# RFMC_ADC.net
KiCad netlist of a schematic drawn in Altium Designer
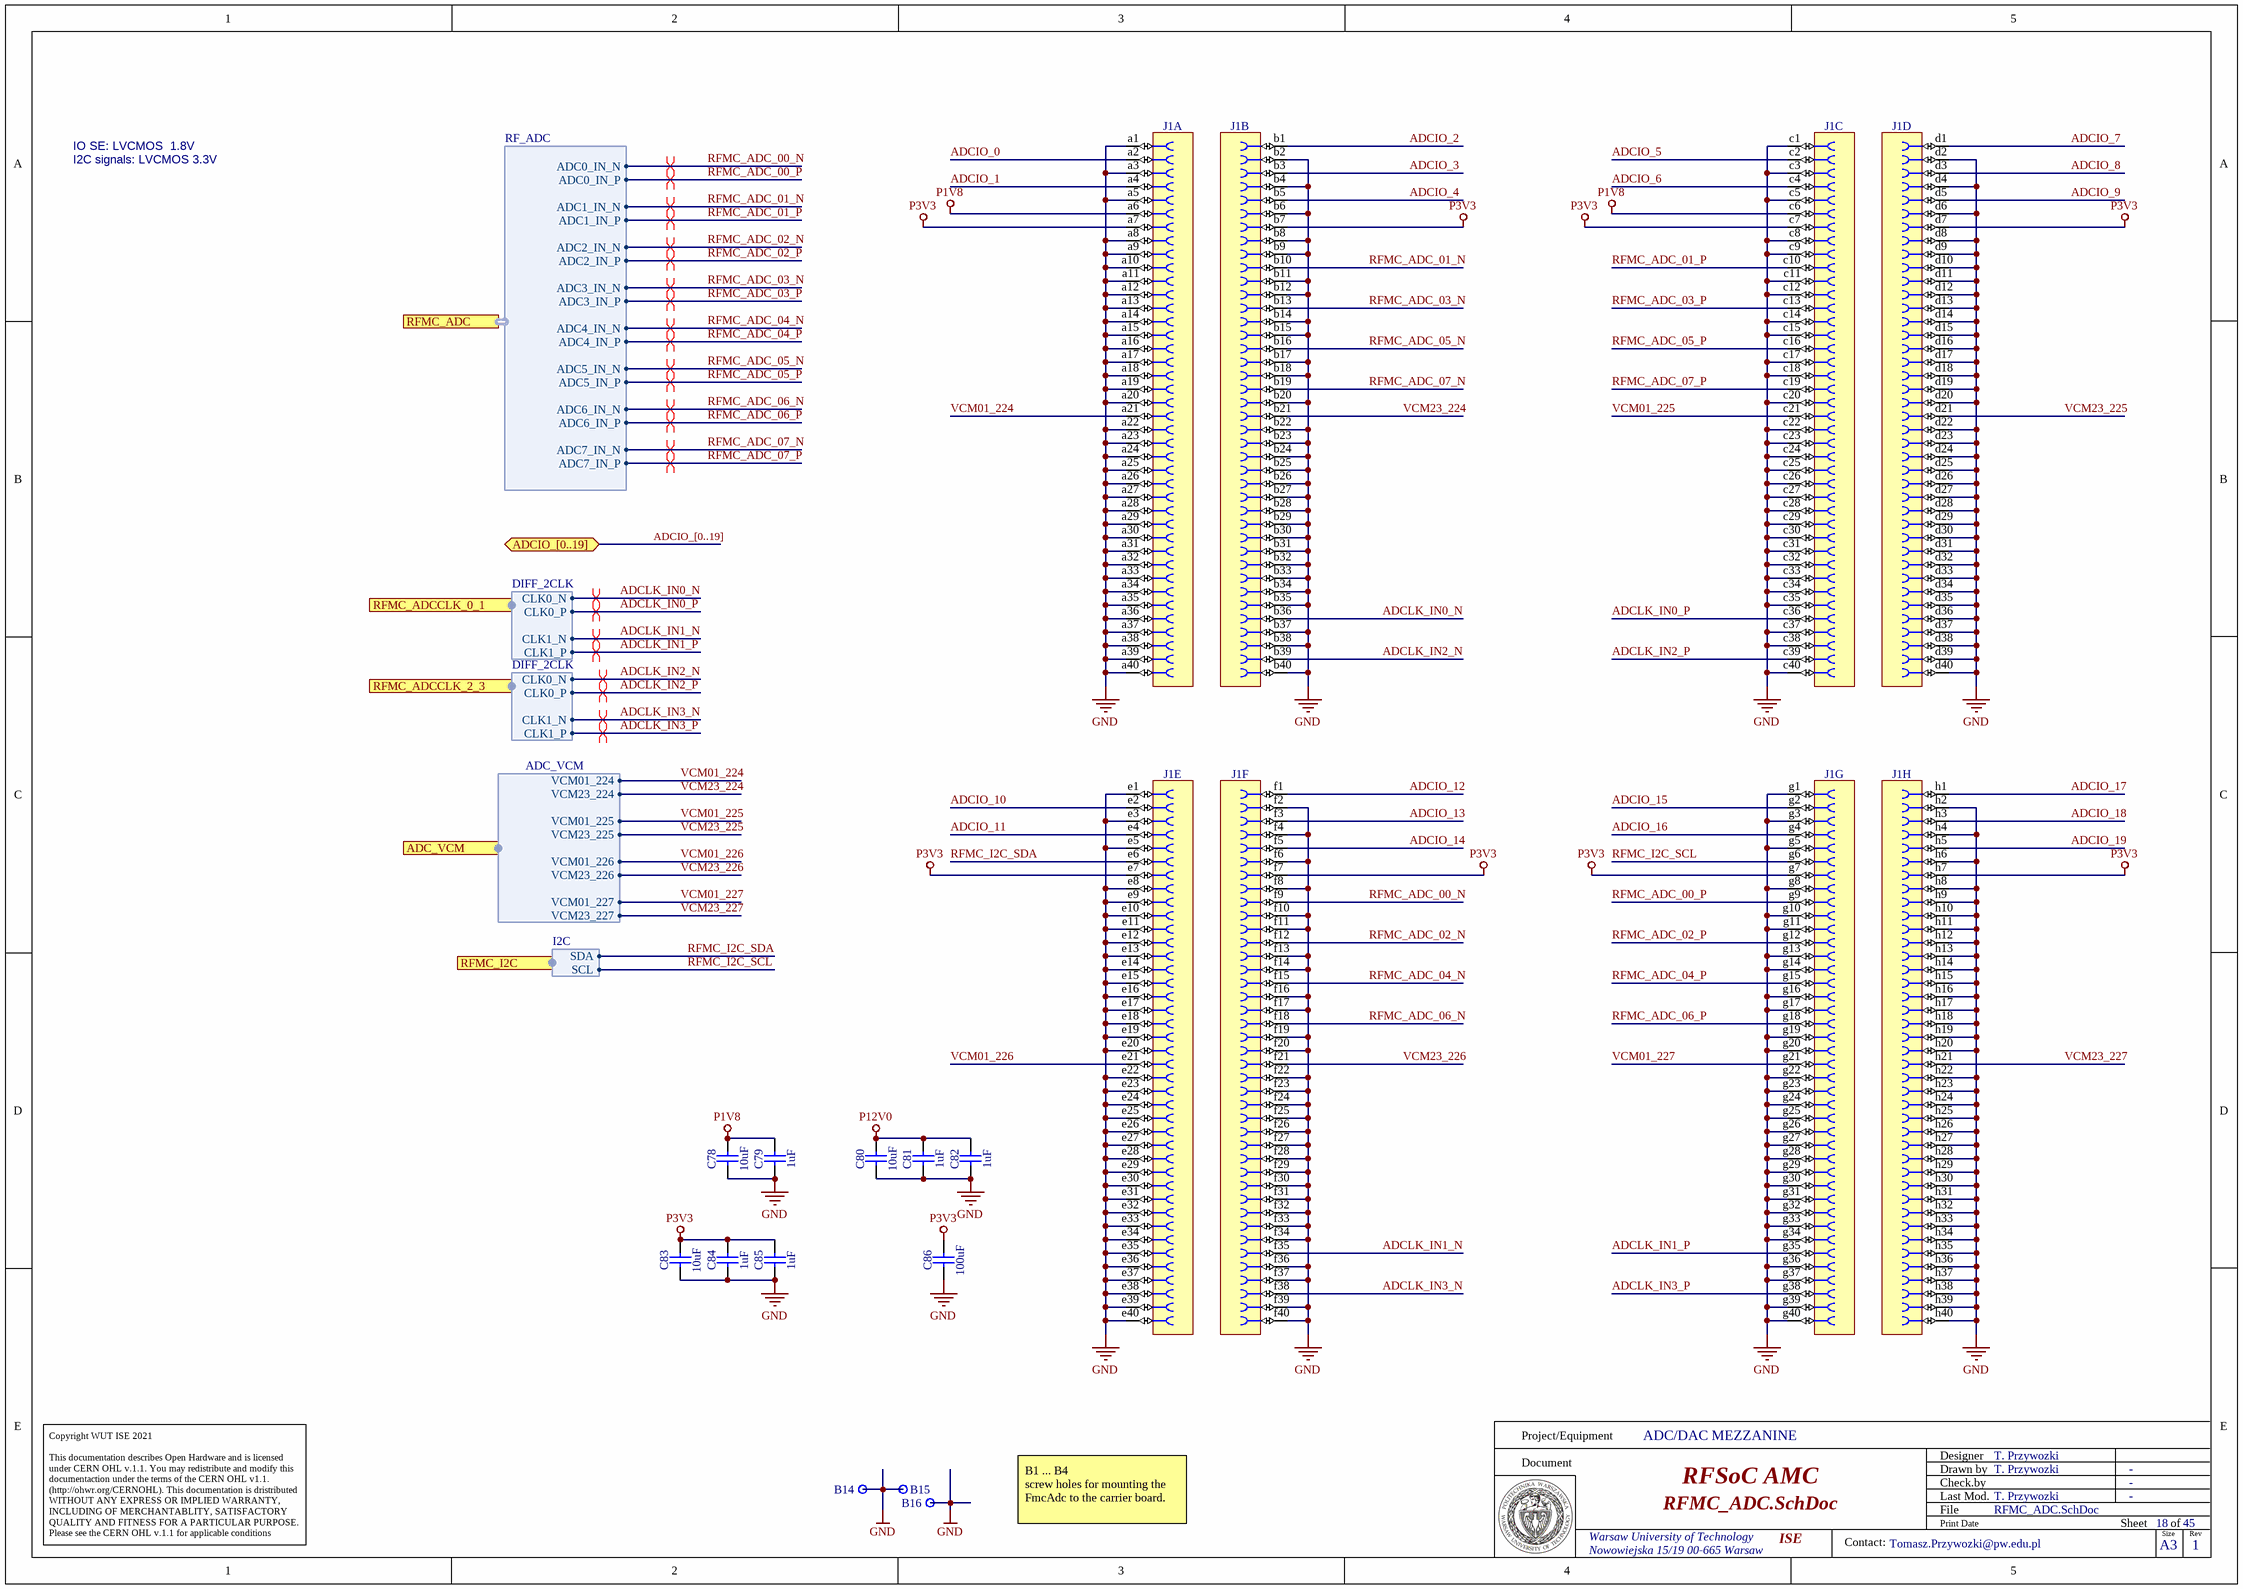
[diagram p0: RFMC_ADC.SchDoc]

(export (version "E")
  (design (tool "Eeschema 10.0.6"))
  (components
    (comp (ref "B14")
      (value "Plated Hole")
      (footprint "MTG270_500")
      (description "Single Terminal Socket")
      (fields (field (name "PART NUMBER") "PLATED_HOLE2.7_PAD5.0") (field (name "AUTHOR") "CERN DEM JMW"))
      (libsource (lib "Eletro-mechanical") (part "Single Terminal Socket"))
    )
    (comp (ref "B15")
      (value "Plated Hole")
      (footprint "MTG270_500")
      (description "Single Terminal Socket")
      (fields (field (name "PART NUMBER") "PLATED_HOLE2.7_PAD5.0") (field (name "AUTHOR") "CERN DEM JMW"))
      (libsource (lib "Eletro-mechanical") (part "Single Terminal Socket"))
    )
    (comp (ref "B16")
      (value "Plated Hole")
      (footprint "MTG270_500")
      (description "Single Terminal Socket")
      (fields (field (name "PART NUMBER") "PLATED_HOLE2.7_PAD5.0") (field (name "AUTHOR") "CERN DEM JMW"))
      (libsource (lib "Eletro-mechanical") (part "Single Terminal Socket"))
    )
    (comp (ref "C78")
      (value "10uF")
      (footprint "CAPC1608X80N")
      (description "Non-polarised capacitor")
      (fields
        (field (name "PART NUMBER") "CC0603_10UF_10V_10%_X5R")
        (field (name "VOLTAGE") "10V")
        (field (name "AUTHOR") "CERN DEM JLC")
      )
      (libsource (lib "Capacitors") (part "Capacitor - non polarized"))
    )
    (comp (ref "C79")
      (value "1uF")
      (footprint "CAPC1005X55N")
      (description "Non-polarised capacitor")
      (fields
        (field (name "PART NUMBER") "CC0402_1UF_16V_10%_X5R")
        (field (name "VOLTAGE") "16V")
        (field (name "AUTHOR") "CERN DEM JLC")
      )
      (libsource (lib "Capacitors") (part "Capacitor - non polarized"))
    )
    (comp (ref "C80")
      (value "10uF")
      (footprint "CAPC1608X80N")
      (description "Non-polarised capacitor")
      (fields
        (field (name "PART NUMBER") "CC0603_10UF_10V_10%_X5R")
        (field (name "VOLTAGE") "10V")
        (field (name "AUTHOR") "CERN DEM JLC")
      )
      (libsource (lib "Capacitors") (part "Capacitor - non polarized"))
    )
    (comp (ref "C81")
      (value "1uF")
      (footprint "CAPC1005X55N")
      (description "Non-polarised capacitor")
      (fields
        (field (name "PART NUMBER") "CC0402_1UF_16V_10%_X5R")
        (field (name "VOLTAGE") "16V")
        (field (name "AUTHOR") "CERN DEM JLC")
      )
      (libsource (lib "Capacitors") (part "Capacitor - non polarized"))
    )
    (comp (ref "C82")
      (value "1uF")
      (footprint "CAPC1005X55N")
      (description "Non-polarised capacitor")
      (fields
        (field (name "PART NUMBER") "CC0402_1UF_16V_10%_X5R")
        (field (name "VOLTAGE") "16V")
        (field (name "AUTHOR") "CERN DEM JLC")
      )
      (libsource (lib "Capacitors") (part "Capacitor - non polarized"))
    )
    (comp (ref "C83")
      (value "10uF")
      (footprint "CAPC1608X80N")
      (description "Non-polarised capacitor")
      (fields
        (field (name "PART NUMBER") "CC0603_10UF_10V_10%_X5R")
        (field (name "VOLTAGE") "10V")
        (field (name "AUTHOR") "CERN DEM JLC")
      )
      (libsource (lib "Capacitors") (part "Capacitor - non polarized"))
    )
    (comp (ref "C84")
      (value "1uF")
      (footprint "CAPC1005X55N")
      (description "Non-polarised capacitor")
      (fields
        (field (name "PART NUMBER") "CC0402_1UF_16V_10%_X5R")
        (field (name "VOLTAGE") "16V")
        (field (name "AUTHOR") "CERN DEM JLC")
      )
      (libsource (lib "Capacitors") (part "Capacitor - non polarized"))
    )
    (comp (ref "C85")
      (value "1uF")
      (footprint "CAPC1005X55N")
      (description "Non-polarised capacitor")
      (fields
        (field (name "PART NUMBER") "CC0402_1UF_16V_10%_X5R")
        (field (name "VOLTAGE") "16V")
        (field (name "AUTHOR") "CERN DEM JLC")
      )
      (libsource (lib "Capacitors") (part "Capacitor - non polarized"))
    )
    (comp (ref "C86")
      (value "100uF")
      (footprint "CAPC3216X180N")
      (description "Non-polarised capacitor")
      (fields
        (field (name "VOLTAGE") "6.3V")
        (field (name "TOLERANCE") "±10%")
        (field (name "AUTHOR") "CERN DEM JLC")
      )
      (libsource (lib "Capacitors") (part "Capacitor - non polarized"))
    )
    (comp (ref "J1")
      (value "~")
      (footprint "SAMTEC_LPAF-40-03.0-S-08")
      (description "Connector 320 Female contacts in 8 row abcdef")
      (fields
        (field (name "PART NUMBER") "SAMTEC_LPAF-40-03.0-S-08-2-K")
        (field (name "MANUFACTURER") "SAMTEC")
        (field (name "AUTHOR") "CERN DEM BC")
      )
      (libsource (lib "Connectors") (part "Connector 320 Female (8x40) (abcdefgh)"))
    )
  )
  (nets
    (net (code "5") (name "/ADCIO_0") (class "Default")
      (node (ref "J1") (pin "a2") (pinfunction "a2_a2") (pintype "bidirectional"))
    )
    (net (code "6") (name "/ADCIO_1") (class "Default")
      (node (ref "J1") (pin "a4") (pinfunction "a4_a4") (pintype "bidirectional"))
    )
    (net (code "7") (name "/ADCIO_2") (class "Default")
      (node (ref "J1") (pin "b1") (pinfunction "b1_b1") (pintype "bidirectional"))
    )
    (net (code "8") (name "/ADCIO_3") (class "Default")
      (node (ref "J1") (pin "b3") (pinfunction "b3_b3") (pintype "bidirectional"))
    )
    (net (code "9") (name "/ADCIO_4") (class "Default")
      (node (ref "J1") (pin "b5") (pinfunction "b5_b5") (pintype "bidirectional"))
    )
    (net (code "10") (name "/ADCIO_5") (class "Default")
      (node (ref "J1") (pin "c2") (pinfunction "c2_c2") (pintype "bidirectional"))
    )
    (net (code "11") (name "/ADCIO_6") (class "Default")
      (node (ref "J1") (pin "c4") (pinfunction "c4_c4") (pintype "bidirectional"))
    )
    (net (code "12") (name "/ADCIO_7") (class "Default")
      (node (ref "J1") (pin "d1") (pinfunction "d1_d1") (pintype "bidirectional"))
    )
    (net (code "13") (name "/ADCIO_8") (class "Default")
      (node (ref "J1") (pin "d3") (pinfunction "d3_d3") (pintype "bidirectional"))
    )
    (net (code "14") (name "/ADCIO_9") (class "Default")
      (node (ref "J1") (pin "d5") (pinfunction "d5_d5") (pintype "bidirectional"))
    )
    (net (code "15") (name "/ADCIO_10") (class "Default")
      (node (ref "J1") (pin "e2") (pinfunction "e2_e2") (pintype "bidirectional"))
    )
    (net (code "16") (name "/ADCIO_11") (class "Default")
      (node (ref "J1") (pin "e4") (pinfunction "e4_e4") (pintype "bidirectional"))
    )
    (net (code "17") (name "/ADCIO_12") (class "Default")
      (node (ref "J1") (pin "f1") (pinfunction "f1_f1") (pintype "bidirectional"))
    )
    (net (code "18") (name "/ADCIO_13") (class "Default")
      (node (ref "J1") (pin "f3") (pinfunction "f3_f3") (pintype "bidirectional"))
    )
    (net (code "19") (name "/ADCIO_14") (class "Default")
      (node (ref "J1") (pin "f5") (pinfunction "f5_f5") (pintype "bidirectional"))
    )
    (net (code "20") (name "/ADCIO_15") (class "Default")
      (node (ref "J1") (pin "g2") (pinfunction "g2_g2") (pintype "bidirectional"))
    )
    (net (code "21") (name "/ADCIO_16") (class "Default")
      (node (ref "J1") (pin "g4") (pinfunction "g4_g4") (pintype "bidirectional"))
    )
    (net (code "22") (name "/ADCIO_17") (class "Default")
      (node (ref "J1") (pin "h1") (pinfunction "h1_h1") (pintype "bidirectional"))
    )
    (net (code "23") (name "/ADCIO_18") (class "Default")
      (node (ref "J1") (pin "h3") (pinfunction "h3_h3") (pintype "bidirectional"))
    )
    (net (code "24") (name "/ADCIO_19") (class "Default")
      (node (ref "J1") (pin "h5") (pinfunction "h5_h5") (pintype "bidirectional"))
    )
    (net (code "26") (name "/ADCLK_IN0_N") (class "Default")
      (node (ref "J1") (pin "b36") (pinfunction "b36_b36") (pintype "bidirectional"))
    )
    (net (code "27") (name "/ADCLK_IN0_P") (class "Default")
      (node (ref "J1") (pin "c36") (pinfunction "c36_c36") (pintype "bidirectional"))
    )
    (net (code "28") (name "/ADCLK_IN1_N") (class "Default")
      (node (ref "J1") (pin "f35") (pinfunction "f35_f35") (pintype "bidirectional"))
    )
    (net (code "29") (name "/ADCLK_IN1_P") (class "Default")
      (node (ref "J1") (pin "g35") (pinfunction "g35_g35") (pintype "bidirectional"))
    )
    (net (code "30") (name "/ADCLK_IN2_N") (class "Default")
      (node (ref "J1") (pin "b39") (pinfunction "b39_b39") (pintype "bidirectional"))
    )
    (net (code "31") (name "/ADCLK_IN2_P") (class "Default")
      (node (ref "J1") (pin "c39") (pinfunction "c39_c39") (pintype "bidirectional"))
    )
    (net (code "32") (name "/ADCLK_IN3_N") (class "Default")
      (node (ref "J1") (pin "f38") (pinfunction "f38_f38") (pintype "bidirectional"))
    )
    (net (code "33") (name "/ADCLK_IN3_P") (class "Default")
      (node (ref "J1") (pin "g38") (pinfunction "g38_g38") (pintype "bidirectional"))
    )
    (net (code "34") (name "/RFMC_ADC_00_N") (class "Default")
      (node (ref "J1") (pin "f9") (pinfunction "f9_f9") (pintype "bidirectional"))
    )
    (net (code "35") (name "/RFMC_ADC_00_P") (class "Default")
      (node (ref "J1") (pin "g9") (pinfunction "g9_g9") (pintype "bidirectional"))
    )
    (net (code "36") (name "/RFMC_ADC_01_N") (class "Default")
      (node (ref "J1") (pin "b10") (pinfunction "b10_b10") (pintype "bidirectional"))
    )
    (net (code "37") (name "/RFMC_ADC_01_P") (class "Default")
      (node (ref "J1") (pin "c10") (pinfunction "c10_c10") (pintype "bidirectional"))
    )
    (net (code "38") (name "/RFMC_ADC_02_N") (class "Default")
      (node (ref "J1") (pin "f12") (pinfunction "f12_f12") (pintype "bidirectional"))
    )
    (net (code "39") (name "/RFMC_ADC_02_P") (class "Default")
      (node (ref "J1") (pin "g12") (pinfunction "g12_g12") (pintype "bidirectional"))
    )
    (net (code "40") (name "/RFMC_ADC_03_N") (class "Default")
      (node (ref "J1") (pin "b13") (pinfunction "b13_b13") (pintype "bidirectional"))
    )
    (net (code "41") (name "/RFMC_ADC_03_P") (class "Default")
      (node (ref "J1") (pin "c13") (pinfunction "c13_c13") (pintype "bidirectional"))
    )
    (net (code "42") (name "/RFMC_ADC_04_N") (class "Default")
      (node (ref "J1") (pin "f15") (pinfunction "f15_f15") (pintype "bidirectional"))
    )
    (net (code "43") (name "/RFMC_ADC_04_P") (class "Default")
      (node (ref "J1") (pin "g15") (pinfunction "g15_g15") (pintype "bidirectional"))
    )
    (net (code "44") (name "/RFMC_ADC_05_N") (class "Default")
      (node (ref "J1") (pin "b16") (pinfunction "b16_b16") (pintype "bidirectional"))
    )
    (net (code "45") (name "/RFMC_ADC_05_P") (class "Default")
      (node (ref "J1") (pin "c16") (pinfunction "c16_c16") (pintype "bidirectional"))
    )
    (net (code "46") (name "/RFMC_ADC_06_N") (class "Default")
      (node (ref "J1") (pin "f18") (pinfunction "f18_f18") (pintype "bidirectional"))
    )
    (net (code "47") (name "/RFMC_ADC_06_P") (class "Default")
      (node (ref "J1") (pin "g18") (pinfunction "g18_g18") (pintype "bidirectional"))
    )
    (net (code "48") (name "/RFMC_ADC_07_N") (class "Default")
      (node (ref "J1") (pin "b19") (pinfunction "b19_b19") (pintype "bidirectional"))
    )
    (net (code "49") (name "/RFMC_ADC_07_P") (class "Default")
      (node (ref "J1") (pin "c19") (pinfunction "c19_c19") (pintype "bidirectional"))
    )
    (net (code "50") (name "/RFMC_I2C_SCL") (class "Default")
      (node (ref "J1") (pin "g6") (pinfunction "g6_g6") (pintype "bidirectional"))
    )
    (net (code "51") (name "/RFMC_I2C_SDA") (class "Default")
      (node (ref "J1") (pin "e6") (pinfunction "e6_e6") (pintype "bidirectional"))
    )
    (net (code "52") (name "/VCM01_224") (class "Default")
      (node (ref "J1") (pin "a21") (pinfunction "a21_a21") (pintype "bidirectional"))
    )
    (net (code "53") (name "/VCM01_225") (class "Default")
      (node (ref "J1") (pin "c21") (pinfunction "c21_c21") (pintype "bidirectional"))
    )
    (net (code "54") (name "/VCM01_226") (class "Default")
      (node (ref "J1") (pin "e21") (pinfunction "e21_e21") (pintype "bidirectional"))
    )
    (net (code "55") (name "/VCM01_227") (class "Default")
      (node (ref "J1") (pin "g21") (pinfunction "g21_g21") (pintype "bidirectional"))
    )
    (net (code "56") (name "/VCM23_224") (class "Default")
      (node (ref "J1") (pin "b21") (pinfunction "b21_b21") (pintype "bidirectional"))
    )
    (net (code "57") (name "/VCM23_225") (class "Default")
      (node (ref "J1") (pin "d21") (pinfunction "d21_d21") (pintype "bidirectional"))
    )
    (net (code "58") (name "/VCM23_226") (class "Default")
      (node (ref "J1") (pin "f21") (pinfunction "f21_f21") (pintype "bidirectional"))
    )
    (net (code "59") (name "/VCM23_227") (class "Default")
      (node (ref "J1") (pin "h21") (pinfunction "h21_h21") (pintype "bidirectional"))
    )
    (net (code "64") (name "GND") (class "Default")
      (node (ref "B14") (pin "1") (pinfunction "1_1") (pintype "bidirectional"))
      (node (ref "B15") (pin "1") (pinfunction "1_1") (pintype "bidirectional"))
      (node (ref "B16") (pin "1") (pinfunction "1_1") (pintype "bidirectional"))
      (node (ref "C78") (pin "1") (pinfunction "1_1") (pintype "passive"))
      (node (ref "C79") (pin "2") (pinfunction "2_2") (pintype "passive"))
      (node (ref "C80") (pin "1") (pinfunction "1_1") (pintype "passive"))
      (node (ref "C81") (pin "2") (pinfunction "2_2") (pintype "passive"))
      (node (ref "C82") (pin "2") (pinfunction "2_2") (pintype "passive"))
      (node (ref "C83") (pin "1") (pinfunction "1_1") (pintype "passive"))
      (node (ref "C84") (pin "2") (pinfunction "2_2") (pintype "passive"))
      (node (ref "C85") (pin "2") (pinfunction "2_2") (pintype "passive"))
      (node (ref "C86") (pin "1") (pinfunction "1_1") (pintype "passive"))
      (node (ref "J1") (pin "a1") (pinfunction "a1_a1") (pintype "bidirectional"))
      (node (ref "J1") (pin "a10") (pinfunction "a10_a10") (pintype "bidirectional"))
      (node (ref "J1") (pin "a11") (pinfunction "a11_a11") (pintype "bidirectional"))
      (node (ref "J1") (pin "a12") (pinfunction "a12_a12") (pintype "bidirectional"))
      (node (ref "J1") (pin "a13") (pinfunction "a13_a13") (pintype "bidirectional"))
      (node (ref "J1") (pin "a14") (pinfunction "a14_a14") (pintype "bidirectional"))
      (node (ref "J1") (pin "a15") (pinfunction "a15_a15") (pintype "bidirectional"))
      (node (ref "J1") (pin "a16") (pinfunction "a16_a16") (pintype "bidirectional"))
      (node (ref "J1") (pin "a17") (pinfunction "a17_a17") (pintype "bidirectional"))
      (node (ref "J1") (pin "a18") (pinfunction "a18_a18") (pintype "bidirectional"))
      (node (ref "J1") (pin "a19") (pinfunction "a19_a19") (pintype "bidirectional"))
      (node (ref "J1") (pin "a20") (pinfunction "a20_a20") (pintype "bidirectional"))
      (node (ref "J1") (pin "a22") (pinfunction "a22_a22") (pintype "bidirectional"))
      (node (ref "J1") (pin "a23") (pinfunction "a23_a23") (pintype "bidirectional"))
      (node (ref "J1") (pin "a24") (pinfunction "a24_a24") (pintype "bidirectional"))
      (node (ref "J1") (pin "a25") (pinfunction "a25_a25") (pintype "bidirectional"))
      (node (ref "J1") (pin "a26") (pinfunction "a26_a26") (pintype "bidirectional"))
      (node (ref "J1") (pin "a27") (pinfunction "a27_a27") (pintype "bidirectional"))
      (node (ref "J1") (pin "a28") (pinfunction "a28_a28") (pintype "bidirectional"))
      (node (ref "J1") (pin "a29") (pinfunction "a29_a29") (pintype "bidirectional"))
      (node (ref "J1") (pin "a3") (pinfunction "a3_a3") (pintype "bidirectional"))
      (node (ref "J1") (pin "a30") (pinfunction "a30_a30") (pintype "bidirectional"))
      (node (ref "J1") (pin "a31") (pinfunction "a31_a31") (pintype "bidirectional"))
      (node (ref "J1") (pin "a32") (pinfunction "a32_a32") (pintype "bidirectional"))
      (node (ref "J1") (pin "a33") (pinfunction "a33_a33") (pintype "bidirectional"))
      (node (ref "J1") (pin "a34") (pinfunction "a34_a34") (pintype "bidirectional"))
      (node (ref "J1") (pin "a35") (pinfunction "a35_a35") (pintype "bidirectional"))
      (node (ref "J1") (pin "a36") (pinfunction "a36_a36") (pintype "bidirectional"))
      (node (ref "J1") (pin "a37") (pinfunction "a37_a37") (pintype "bidirectional"))
      (node (ref "J1") (pin "a38") (pinfunction "a38_a38") (pintype "bidirectional"))
      (node (ref "J1") (pin "a39") (pinfunction "a39_a39") (pintype "bidirectional"))
      (node (ref "J1") (pin "a40") (pinfunction "a40_a40") (pintype "bidirectional"))
      (node (ref "J1") (pin "a5") (pinfunction "a5_a5") (pintype "bidirectional"))
      (node (ref "J1") (pin "a8") (pinfunction "a8_a8") (pintype "bidirectional"))
      (node (ref "J1") (pin "a9") (pinfunction "a9_a9") (pintype "bidirectional"))
      (node (ref "J1") (pin "b11") (pinfunction "b11_b11") (pintype "bidirectional"))
      (node (ref "J1") (pin "b12") (pinfunction "b12_b12") (pintype "bidirectional"))
      (node (ref "J1") (pin "b14") (pinfunction "b14_b14") (pintype "bidirectional"))
      (node (ref "J1") (pin "b15") (pinfunction "b15_b15") (pintype "bidirectional"))
      (node (ref "J1") (pin "b17") (pinfunction "b17_b17") (pintype "bidirectional"))
      (node (ref "J1") (pin "b18") (pinfunction "b18_b18") (pintype "bidirectional"))
      (node (ref "J1") (pin "b2") (pinfunction "b2_b2") (pintype "bidirectional"))
      (node (ref "J1") (pin "b20") (pinfunction "b20_b20") (pintype "bidirectional"))
      (node (ref "J1") (pin "b22") (pinfunction "b22_b22") (pintype "bidirectional"))
      (node (ref "J1") (pin "b23") (pinfunction "b23_b23") (pintype "bidirectional"))
      (node (ref "J1") (pin "b24") (pinfunction "b24_b24") (pintype "bidirectional"))
      (node (ref "J1") (pin "b25") (pinfunction "b25_b25") (pintype "bidirectional"))
      (node (ref "J1") (pin "b26") (pinfunction "b26_b26") (pintype "bidirectional"))
      (node (ref "J1") (pin "b27") (pinfunction "b27_b27") (pintype "bidirectional"))
      (node (ref "J1") (pin "b28") (pinfunction "b28_b28") (pintype "bidirectional"))
      (node (ref "J1") (pin "b29") (pinfunction "b29_b29") (pintype "bidirectional"))
      (node (ref "J1") (pin "b30") (pinfunction "b30_b30") (pintype "bidirectional"))
      (node (ref "J1") (pin "b31") (pinfunction "b31_b31") (pintype "bidirectional"))
      (node (ref "J1") (pin "b32") (pinfunction "b32_b32") (pintype "bidirectional"))
      (node (ref "J1") (pin "b33") (pinfunction "b33_b33") (pintype "bidirectional"))
      (node (ref "J1") (pin "b34") (pinfunction "b34_b34") (pintype "bidirectional"))
      (node (ref "J1") (pin "b35") (pinfunction "b35_b35") (pintype "bidirectional"))
      (node (ref "J1") (pin "b37") (pinfunction "b37_b37") (pintype "bidirectional"))
      (node (ref "J1") (pin "b38") (pinfunction "b38_b38") (pintype "bidirectional"))
      (node (ref "J1") (pin "b4") (pinfunction "b4_b4") (pintype "bidirectional"))
      (node (ref "J1") (pin "b40") (pinfunction "b40_b40") (pintype "bidirectional"))
      (node (ref "J1") (pin "b6") (pinfunction "b6_b6") (pintype "bidirectional"))
      (node (ref "J1") (pin "b8") (pinfunction "b8_b8") (pintype "bidirectional"))
      (node (ref "J1") (pin "b9") (pinfunction "b9_b9") (pintype "bidirectional"))
      (node (ref "J1") (pin "c1") (pinfunction "c1_c1") (pintype "bidirectional"))
      (node (ref "J1") (pin "c11") (pinfunction "c11_c11") (pintype "bidirectional"))
      (node (ref "J1") (pin "c12") (pinfunction "c12_c12") (pintype "bidirectional"))
      (node (ref "J1") (pin "c14") (pinfunction "c14_c14") (pintype "bidirectional"))
      (node (ref "J1") (pin "c15") (pinfunction "c15_c15") (pintype "bidirectional"))
      (node (ref "J1") (pin "c17") (pinfunction "c17_c17") (pintype "bidirectional"))
      (node (ref "J1") (pin "c18") (pinfunction "c18_c18") (pintype "bidirectional"))
      (node (ref "J1") (pin "c20") (pinfunction "c20_c20") (pintype "bidirectional"))
      (node (ref "J1") (pin "c22") (pinfunction "c22_c22") (pintype "bidirectional"))
      (node (ref "J1") (pin "c23") (pinfunction "c23_c23") (pintype "bidirectional"))
      (node (ref "J1") (pin "c24") (pinfunction "c24_c24") (pintype "bidirectional"))
      (node (ref "J1") (pin "c25") (pinfunction "c25_c25") (pintype "bidirectional"))
      (node (ref "J1") (pin "c26") (pinfunction "c26_c26") (pintype "bidirectional"))
      (node (ref "J1") (pin "c27") (pinfunction "c27_c27") (pintype "bidirectional"))
      (node (ref "J1") (pin "c28") (pinfunction "c28_c28") (pintype "bidirectional"))
      (node (ref "J1") (pin "c29") (pinfunction "c29_c29") (pintype "bidirectional"))
      (node (ref "J1") (pin "c3") (pinfunction "c3_c3") (pintype "bidirectional"))
      (node (ref "J1") (pin "c30") (pinfunction "c30_c30") (pintype "bidirectional"))
      (node (ref "J1") (pin "c31") (pinfunction "c31_c31") (pintype "bidirectional"))
      (node (ref "J1") (pin "c32") (pinfunction "c32_c32") (pintype "bidirectional"))
      (node (ref "J1") (pin "c33") (pinfunction "c33_c33") (pintype "bidirectional"))
      (node (ref "J1") (pin "c34") (pinfunction "c34_c34") (pintype "bidirectional"))
      (node (ref "J1") (pin "c35") (pinfunction "c35_c35") (pintype "bidirectional"))
      (node (ref "J1") (pin "c37") (pinfunction "c37_c37") (pintype "bidirectional"))
      (node (ref "J1") (pin "c38") (pinfunction "c38_c38") (pintype "bidirectional"))
      (node (ref "J1") (pin "c40") (pinfunction "c40_c40") (pintype "bidirectional"))
      (node (ref "J1") (pin "c5") (pinfunction "c5_c5") (pintype "bidirectional"))
      (node (ref "J1") (pin "c8") (pinfunction "c8_c8") (pintype "bidirectional"))
      (node (ref "J1") (pin "c9") (pinfunction "c9_c9") (pintype "bidirectional"))
      (node (ref "J1") (pin "d10") (pinfunction "d10_d10") (pintype "bidirectional"))
      (node (ref "J1") (pin "d11") (pinfunction "d11_d11") (pintype "bidirectional"))
      (node (ref "J1") (pin "d12") (pinfunction "d12_d12") (pintype "bidirectional"))
      (node (ref "J1") (pin "d13") (pinfunction "d13_d13") (pintype "bidirectional"))
      (node (ref "J1") (pin "d14") (pinfunction "d14_d14") (pintype "bidirectional"))
      (node (ref "J1") (pin "d15") (pinfunction "d15_d15") (pintype "bidirectional"))
      (node (ref "J1") (pin "d16") (pinfunction "d16_d16") (pintype "bidirectional"))
      (node (ref "J1") (pin "d17") (pinfunction "d17_d17") (pintype "bidirectional"))
      (node (ref "J1") (pin "d18") (pinfunction "d18_d18") (pintype "bidirectional"))
      (node (ref "J1") (pin "d19") (pinfunction "d19_d19") (pintype "bidirectional"))
      (node (ref "J1") (pin "d2") (pinfunction "d2_d2") (pintype "bidirectional"))
      (node (ref "J1") (pin "d20") (pinfunction "d20_d20") (pintype "bidirectional"))
      (node (ref "J1") (pin "d22") (pinfunction "d22_d22") (pintype "bidirectional"))
      (node (ref "J1") (pin "d23") (pinfunction "d23_d23") (pintype "bidirectional"))
      (node (ref "J1") (pin "d24") (pinfunction "d24_d24") (pintype "bidirectional"))
      (node (ref "J1") (pin "d25") (pinfunction "d25_d25") (pintype "bidirectional"))
      (node (ref "J1") (pin "d26") (pinfunction "d26_d26") (pintype "bidirectional"))
      (node (ref "J1") (pin "d27") (pinfunction "d27_d27") (pintype "bidirectional"))
      (node (ref "J1") (pin "d28") (pinfunction "d28_d28") (pintype "bidirectional"))
      (node (ref "J1") (pin "d29") (pinfunction "d29_d29") (pintype "bidirectional"))
      (node (ref "J1") (pin "d30") (pinfunction "d30_d30") (pintype "bidirectional"))
      (node (ref "J1") (pin "d31") (pinfunction "d31_d31") (pintype "bidirectional"))
      (node (ref "J1") (pin "d32") (pinfunction "d32_d32") (pintype "bidirectional"))
      (node (ref "J1") (pin "d33") (pinfunction "d33_d33") (pintype "bidirectional"))
      (node (ref "J1") (pin "d34") (pinfunction "d34_d34") (pintype "bidirectional"))
      (node (ref "J1") (pin "d35") (pinfunction "d35_d35") (pintype "bidirectional"))
      (node (ref "J1") (pin "d36") (pinfunction "d36_d36") (pintype "bidirectional"))
      (node (ref "J1") (pin "d37") (pinfunction "d37_d37") (pintype "bidirectional"))
      (node (ref "J1") (pin "d38") (pinfunction "d38_d38") (pintype "bidirectional"))
      (node (ref "J1") (pin "d39") (pinfunction "d39_d39") (pintype "bidirectional"))
      (node (ref "J1") (pin "d4") (pinfunction "d4_d4") (pintype "bidirectional"))
      (node (ref "J1") (pin "d40") (pinfunction "d40_d40") (pintype "bidirectional"))
      (node (ref "J1") (pin "d6") (pinfunction "d6_d6") (pintype "bidirectional"))
      (node (ref "J1") (pin "d8") (pinfunction "d8_d8") (pintype "bidirectional"))
      (node (ref "J1") (pin "d9") (pinfunction "d9_d9") (pintype "bidirectional"))
      (node (ref "J1") (pin "e1") (pinfunction "e1_e1") (pintype "bidirectional"))
      (node (ref "J1") (pin "e10") (pinfunction "e10_e10") (pintype "bidirectional"))
      (node (ref "J1") (pin "e11") (pinfunction "e11_e11") (pintype "bidirectional"))
      (node (ref "J1") (pin "e12") (pinfunction "e12_e12") (pintype "bidirectional"))
      (node (ref "J1") (pin "e13") (pinfunction "e13_e13") (pintype "bidirectional"))
      (node (ref "J1") (pin "e14") (pinfunction "e14_e14") (pintype "bidirectional"))
      (node (ref "J1") (pin "e15") (pinfunction "e15_e15") (pintype "bidirectional"))
      (node (ref "J1") (pin "e16") (pinfunction "e16_e16") (pintype "bidirectional"))
      (node (ref "J1") (pin "e17") (pinfunction "e17_e17") (pintype "bidirectional"))
      (node (ref "J1") (pin "e18") (pinfunction "e18_e18") (pintype "bidirectional"))
      (node (ref "J1") (pin "e19") (pinfunction "e19_e19") (pintype "bidirectional"))
      (node (ref "J1") (pin "e20") (pinfunction "e20_e20") (pintype "bidirectional"))
      (node (ref "J1") (pin "e22") (pinfunction "e22_e22") (pintype "bidirectional"))
      (node (ref "J1") (pin "e23") (pinfunction "e23_e23") (pintype "bidirectional"))
      (node (ref "J1") (pin "e24") (pinfunction "e24_e24") (pintype "bidirectional"))
      (node (ref "J1") (pin "e25") (pinfunction "e25_e25") (pintype "bidirectional"))
      (node (ref "J1") (pin "e26") (pinfunction "e26_e26") (pintype "bidirectional"))
      (node (ref "J1") (pin "e27") (pinfunction "e27_e27") (pintype "bidirectional"))
      (node (ref "J1") (pin "e28") (pinfunction "e28_e28") (pintype "bidirectional"))
      (node (ref "J1") (pin "e29") (pinfunction "e29_e29") (pintype "bidirectional"))
      (node (ref "J1") (pin "e3") (pinfunction "e3_e3") (pintype "bidirectional"))
      (node (ref "J1") (pin "e30") (pinfunction "e30_e30") (pintype "bidirectional"))
      (node (ref "J1") (pin "e31") (pinfunction "e31_e31") (pintype "bidirectional"))
      (node (ref "J1") (pin "e32") (pinfunction "e32_e32") (pintype "bidirectional"))
      (node (ref "J1") (pin "e33") (pinfunction "e33_e33") (pintype "bidirectional"))
      (node (ref "J1") (pin "e34") (pinfunction "e34_e34") (pintype "bidirectional"))
      (node (ref "J1") (pin "e35") (pinfunction "e35_e35") (pintype "bidirectional"))
      (node (ref "J1") (pin "e36") (pinfunction "e36_e36") (pintype "bidirectional"))
      (node (ref "J1") (pin "e37") (pinfunction "e37_e37") (pintype "bidirectional"))
      (node (ref "J1") (pin "e38") (pinfunction "e38_e38") (pintype "bidirectional"))
      (node (ref "J1") (pin "e39") (pinfunction "e39_e39") (pintype "bidirectional"))
      (node (ref "J1") (pin "e40") (pinfunction "e40_e40") (pintype "bidirectional"))
      (node (ref "J1") (pin "e5") (pinfunction "e5_e5") (pintype "bidirectional"))
      (node (ref "J1") (pin "e8") (pinfunction "e8_e8") (pintype "bidirectional"))
      (node (ref "J1") (pin "e9") (pinfunction "e9_e9") (pintype "bidirectional"))
      (node (ref "J1") (pin "f10") (pinfunction "f10_f10") (pintype "bidirectional"))
      (node (ref "J1") (pin "f11") (pinfunction "f11_f11") (pintype "bidirectional"))
      (node (ref "J1") (pin "f13") (pinfunction "f13_f13") (pintype "bidirectional"))
      (node (ref "J1") (pin "f14") (pinfunction "f14_f14") (pintype "bidirectional"))
      (node (ref "J1") (pin "f16") (pinfunction "f16_f16") (pintype "bidirectional"))
      (node (ref "J1") (pin "f17") (pinfunction "f17_f17") (pintype "bidirectional"))
      (node (ref "J1") (pin "f19") (pinfunction "f19_f19") (pintype "bidirectional"))
      (node (ref "J1") (pin "f2") (pinfunction "f2_f2") (pintype "bidirectional"))
      (node (ref "J1") (pin "f20") (pinfunction "f20_f20") (pintype "bidirectional"))
      (node (ref "J1") (pin "f22") (pinfunction "f22_f22") (pintype "bidirectional"))
      (node (ref "J1") (pin "f23") (pinfunction "f23_f23") (pintype "bidirectional"))
      (node (ref "J1") (pin "f24") (pinfunction "f24_f24") (pintype "bidirectional"))
      (node (ref "J1") (pin "f25") (pinfunction "f25_f25") (pintype "bidirectional"))
      (node (ref "J1") (pin "f26") (pinfunction "f26_f26") (pintype "bidirectional"))
      (node (ref "J1") (pin "f27") (pinfunction "f27_f27") (pintype "bidirectional"))
      (node (ref "J1") (pin "f28") (pinfunction "f28_f28") (pintype "bidirectional"))
      (node (ref "J1") (pin "f29") (pinfunction "f29_f29") (pintype "bidirectional"))
      (node (ref "J1") (pin "f30") (pinfunction "f30_f30") (pintype "bidirectional"))
      (node (ref "J1") (pin "f31") (pinfunction "f31_f31") (pintype "bidirectional"))
      (node (ref "J1") (pin "f32") (pinfunction "f32_f32") (pintype "bidirectional"))
      (node (ref "J1") (pin "f33") (pinfunction "f33_f33") (pintype "bidirectional"))
      (node (ref "J1") (pin "f34") (pinfunction "f34_f34") (pintype "bidirectional"))
      (node (ref "J1") (pin "f36") (pinfunction "f36_f36") (pintype "bidirectional"))
      (node (ref "J1") (pin "f37") (pinfunction "f37_f37") (pintype "bidirectional"))
      (node (ref "J1") (pin "f39") (pinfunction "f39_f39") (pintype "bidirectional"))
      (node (ref "J1") (pin "f4") (pinfunction "f4_f4") (pintype "bidirectional"))
      (node (ref "J1") (pin "f40") (pinfunction "f40_f40") (pintype "bidirectional"))
      (node (ref "J1") (pin "f6") (pinfunction "f6_f6") (pintype "bidirectional"))
      (node (ref "J1") (pin "f8") (pinfunction "f8_f8") (pintype "bidirectional"))
      (node (ref "J1") (pin "g1") (pinfunction "g1_g1") (pintype "bidirectional"))
      (node (ref "J1") (pin "g10") (pinfunction "g10_g10") (pintype "bidirectional"))
      (node (ref "J1") (pin "g11") (pinfunction "g11_g11") (pintype "bidirectional"))
      (node (ref "J1") (pin "g13") (pinfunction "g13_g13") (pintype "bidirectional"))
      (node (ref "J1") (pin "g14") (pinfunction "g14_g14") (pintype "bidirectional"))
      (node (ref "J1") (pin "g16") (pinfunction "g16_g16") (pintype "bidirectional"))
      (node (ref "J1") (pin "g17") (pinfunction "g17_g17") (pintype "bidirectional"))
      (node (ref "J1") (pin "g19") (pinfunction "g19_g19") (pintype "bidirectional"))
      (node (ref "J1") (pin "g20") (pinfunction "g20_g20") (pintype "bidirectional"))
      (node (ref "J1") (pin "g22") (pinfunction "g22_g22") (pintype "bidirectional"))
      (node (ref "J1") (pin "g23") (pinfunction "g23_g23") (pintype "bidirectional"))
      (node (ref "J1") (pin "g24") (pinfunction "g24_g24") (pintype "bidirectional"))
      (node (ref "J1") (pin "g25") (pinfunction "g25_g25") (pintype "bidirectional"))
      (node (ref "J1") (pin "g26") (pinfunction "g26_g26") (pintype "bidirectional"))
      (node (ref "J1") (pin "g27") (pinfunction "g27_g27") (pintype "bidirectional"))
      (node (ref "J1") (pin "g28") (pinfunction "g28_g28") (pintype "bidirectional"))
      (node (ref "J1") (pin "g29") (pinfunction "g29_g29") (pintype "bidirectional"))
      (node (ref "J1") (pin "g3") (pinfunction "g3_g3") (pintype "bidirectional"))
      (node (ref "J1") (pin "g30") (pinfunction "g30_g30") (pintype "bidirectional"))
      (node (ref "J1") (pin "g31") (pinfunction "g31_g31") (pintype "bidirectional"))
      (node (ref "J1") (pin "g32") (pinfunction "g32_g32") (pintype "bidirectional"))
      (node (ref "J1") (pin "g33") (pinfunction "g33_g33") (pintype "bidirectional"))
      (node (ref "J1") (pin "g34") (pinfunction "g34_g34") (pintype "bidirectional"))
      (node (ref "J1") (pin "g36") (pinfunction "g36_g36") (pintype "bidirectional"))
      (node (ref "J1") (pin "g37") (pinfunction "g37_g37") (pintype "bidirectional"))
      (node (ref "J1") (pin "g39") (pinfunction "g39_g39") (pintype "bidirectional"))
      (node (ref "J1") (pin "g40") (pinfunction "g40_g40") (pintype "bidirectional"))
      (node (ref "J1") (pin "g5") (pinfunction "g5_g5") (pintype "bidirectional"))
      (node (ref "J1") (pin "g8") (pinfunction "g8_g8") (pintype "bidirectional"))
      (node (ref "J1") (pin "h10") (pinfunction "h10_h10") (pintype "bidirectional"))
      (node (ref "J1") (pin "h11") (pinfunction "h11_h11") (pintype "bidirectional"))
      (node (ref "J1") (pin "h12") (pinfunction "h12_h12") (pintype "bidirectional"))
      (node (ref "J1") (pin "h13") (pinfunction "h13_h13") (pintype "bidirectional"))
      (node (ref "J1") (pin "h14") (pinfunction "h14_h14") (pintype "bidirectional"))
      (node (ref "J1") (pin "h15") (pinfunction "h15_h15") (pintype "bidirectional"))
      (node (ref "J1") (pin "h16") (pinfunction "h16_h16") (pintype "bidirectional"))
      (node (ref "J1") (pin "h17") (pinfunction "h17_h17") (pintype "bidirectional"))
      (node (ref "J1") (pin "h18") (pinfunction "h18_h18") (pintype "bidirectional"))
      (node (ref "J1") (pin "h19") (pinfunction "h19_h19") (pintype "bidirectional"))
      (node (ref "J1") (pin "h2") (pinfunction "h2_h2") (pintype "bidirectional"))
      (node (ref "J1") (pin "h20") (pinfunction "h20_h20") (pintype "bidirectional"))
      (node (ref "J1") (pin "h22") (pinfunction "h22_h22") (pintype "bidirectional"))
      (node (ref "J1") (pin "h23") (pinfunction "h23_h23") (pintype "bidirectional"))
      (node (ref "J1") (pin "h24") (pinfunction "h24_h24") (pintype "bidirectional"))
      (node (ref "J1") (pin "h25") (pinfunction "h25_h25") (pintype "bidirectional"))
      (node (ref "J1") (pin "h26") (pinfunction "h26_h26") (pintype "bidirectional"))
      (node (ref "J1") (pin "h27") (pinfunction "h27_h27") (pintype "bidirectional"))
      (node (ref "J1") (pin "h28") (pinfunction "h28_h28") (pintype "bidirectional"))
      (node (ref "J1") (pin "h29") (pinfunction "h29_h29") (pintype "bidirectional"))
      (node (ref "J1") (pin "h30") (pinfunction "h30_h30") (pintype "bidirectional"))
      (node (ref "J1") (pin "h31") (pinfunction "h31_h31") (pintype "bidirectional"))
      (node (ref "J1") (pin "h32") (pinfunction "h32_h32") (pintype "bidirectional"))
      (node (ref "J1") (pin "h33") (pinfunction "h33_h33") (pintype "bidirectional"))
      (node (ref "J1") (pin "h34") (pinfunction "h34_h34") (pintype "bidirectional"))
      (node (ref "J1") (pin "h35") (pinfunction "h35_h35") (pintype "bidirectional"))
      (node (ref "J1") (pin "h36") (pinfunction "h36_h36") (pintype "bidirectional"))
      (node (ref "J1") (pin "h37") (pinfunction "h37_h37") (pintype "bidirectional"))
      (node (ref "J1") (pin "h38") (pinfunction "h38_h38") (pintype "bidirectional"))
      (node (ref "J1") (pin "h39") (pinfunction "h39_h39") (pintype "bidirectional"))
      (node (ref "J1") (pin "h4") (pinfunction "h4_h4") (pintype "bidirectional"))
      (node (ref "J1") (pin "h40") (pinfunction "h40_h40") (pintype "bidirectional"))
      (node (ref "J1") (pin "h6") (pinfunction "h6_h6") (pintype "bidirectional"))
      (node (ref "J1") (pin "h8") (pinfunction "h8_h8") (pintype "bidirectional"))
      (node (ref "J1") (pin "h9") (pinfunction "h9_h9") (pintype "bidirectional"))
    )
    (net (code "65") (name "P1V8") (class "Default")
      (node (ref "C78") (pin "2") (pinfunction "2_2") (pintype "passive"))
      (node (ref "C79") (pin "1") (pinfunction "1_1") (pintype "passive"))
      (node (ref "J1") (pin "a6") (pinfunction "a6_a6") (pintype "bidirectional"))
      (node (ref "J1") (pin "c6") (pinfunction "c6_c6") (pintype "bidirectional"))
    )
    (net (code "66") (name "P3V3") (class "Default")
      (node (ref "C83") (pin "2") (pinfunction "2_2") (pintype "passive"))
      (node (ref "C84") (pin "1") (pinfunction "1_1") (pintype "passive"))
      (node (ref "C85") (pin "1") (pinfunction "1_1") (pintype "passive"))
      (node (ref "C86") (pin "2") (pinfunction "2_2") (pintype "passive"))
      (node (ref "J1") (pin "a7") (pinfunction "a7_a7") (pintype "bidirectional"))
      (node (ref "J1") (pin "b7") (pinfunction "b7_b7") (pintype "bidirectional"))
      (node (ref "J1") (pin "c7") (pinfunction "c7_c7") (pintype "bidirectional"))
      (node (ref "J1") (pin "d7") (pinfunction "d7_d7") (pintype "bidirectional"))
      (node (ref "J1") (pin "e7") (pinfunction "e7_e7") (pintype "bidirectional"))
      (node (ref "J1") (pin "f7") (pinfunction "f7_f7") (pintype "bidirectional"))
      (node (ref "J1") (pin "g7") (pinfunction "g7_g7") (pintype "bidirectional"))
      (node (ref "J1") (pin "h7") (pinfunction "h7_h7") (pintype "bidirectional"))
    )
    (net (code "67") (name "P12V0") (class "Default")
      (node (ref "C80") (pin "2") (pinfunction "2_2") (pintype "passive"))
      (node (ref "C81") (pin "1") (pinfunction "1_1") (pintype "passive"))
      (node (ref "C82") (pin "1") (pinfunction "1_1") (pintype "passive"))
    )
  )
)
